# Connectors.net
KiCad netlist of a schematic drawn in Altium Designer
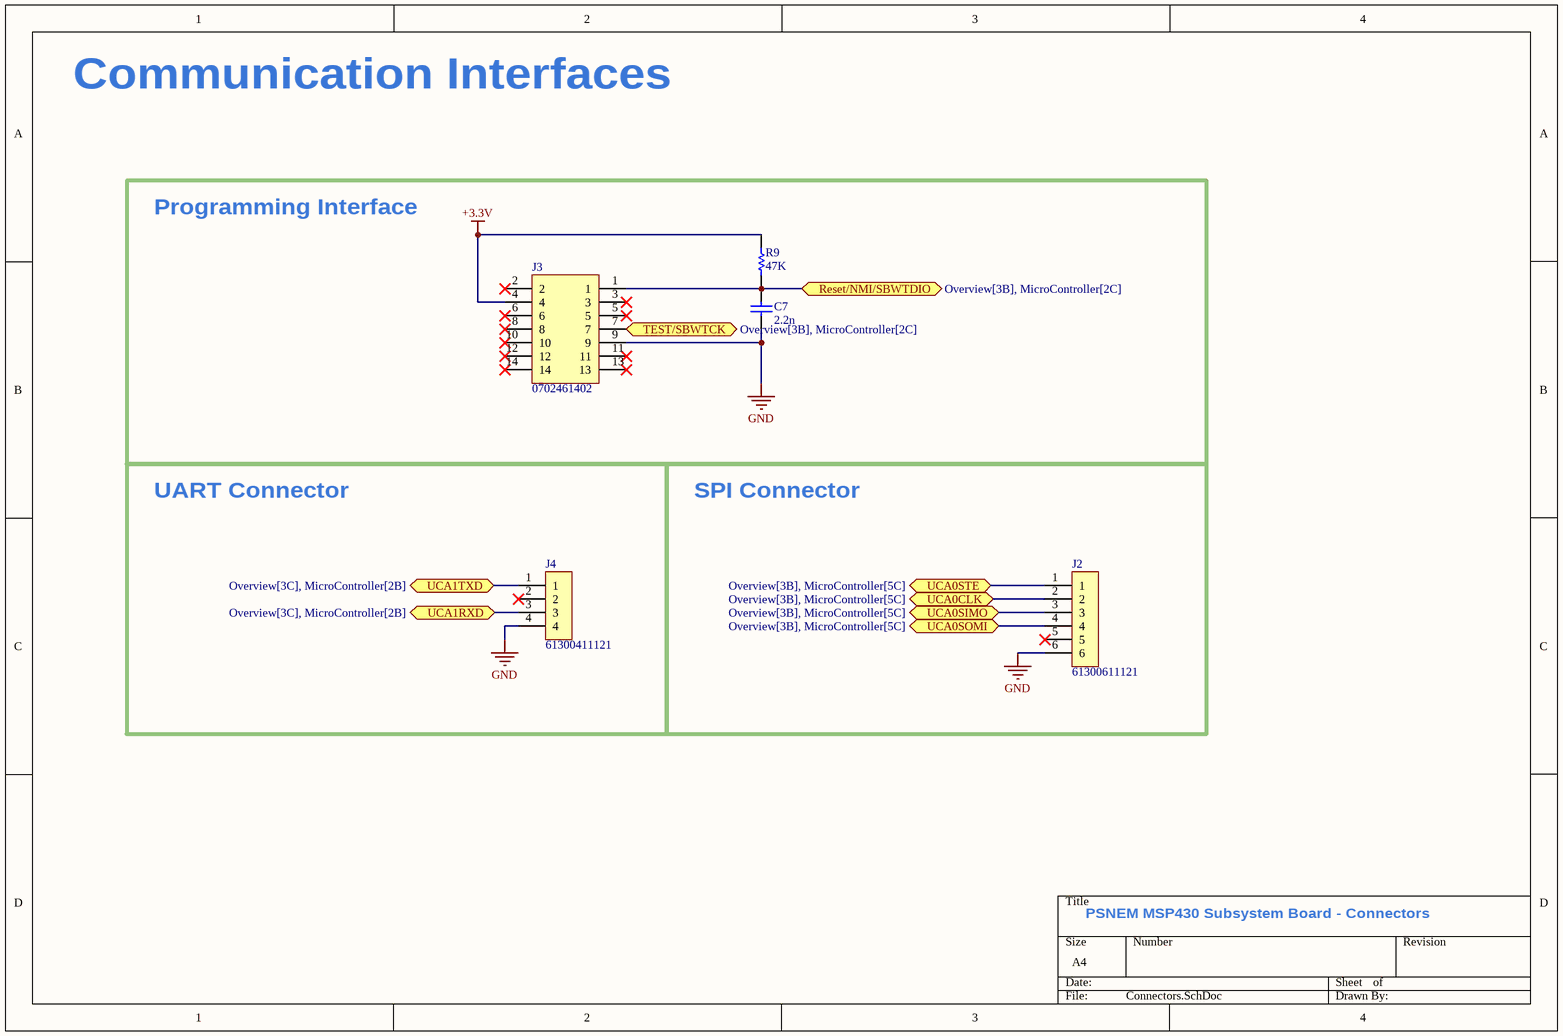
[diagram p0: Connectors.SchDoc]

(export (version "E")
  (design (tool "Eeschema 10.0.6"))
  (components
    (comp (ref "C7")
      (value "2.2n")
      (footprint "0805 Cap")
      (description "2200 pF ±10% 50V Ceramic Capacitor X7R 0805 (2012 Metric)")
      (libsource (lib "Schlib1") (part "CC0805KRX7R9BB222"))
    )
    (comp (ref "J2")
      (value "61300611121")
      (footprint "61300611121")
      (description "CONN HEADER VERT 6POS 2.54MM")
      (libsource (lib "Schlib1") (part "61300611121"))
    )
    (comp (ref "J3")
      (value "0702461402")
      (footprint "0702461402")
      (description "Connector Header Through Hole 14 position 0.100\" (2.54mm)")
      (libsource (lib "Schlib1") (part "0702461402"))
    )
    (comp (ref "J4")
      (value "61300411121")
      (footprint "61300411121")
      (description "Connector Header Through Hole 4 position 0.100\" (2.54mm)")
      (libsource (lib "Schlib1") (part "61300411121"))
    )
    (comp (ref "R9")
      (value "47K")
      (footprint "RESC1608X06N")
      (description "Thin Film Resistors - SMD 0603 0.1% 47Kohm 25ppm SMD")
      (libsource (lib "Schlib1") (part "ERA-3VEB4702V"))
    )
  )
  (nets
    (net (code "1") (name "+3.3V") (class "Default")
      (node (ref "J3") (pin "4") (pinfunction "4_4") (pintype "passive"))
      (node (ref "R9") (pin "2") (pinfunction "2_2") (pintype "passive"))
    )
    (net (code "2") (name "/Reset{slash}NMI{slash}SBWTDIO") (class "Default")
      (node (ref "C7") (pin "2") (pinfunction "2_2") (pintype "passive"))
      (node (ref "J3") (pin "1") (pinfunction "1_1") (pintype "passive"))
      (node (ref "R9") (pin "1") (pinfunction "1_1") (pintype "passive"))
    )
    (net (code "3") (name "/TEST{slash}SBWTCK") (class "Default")
      (node (ref "J3") (pin "7") (pinfunction "7_7") (pintype "passive"))
    )
    (net (code "4") (name "/UCA0CLK") (class "Default")
      (node (ref "J2") (pin "2") (pinfunction "2_2") (pintype "passive"))
    )
    (net (code "5") (name "/UCA0SIMO") (class "Default")
      (node (ref "J2") (pin "3") (pinfunction "3_3") (pintype "passive"))
    )
    (net (code "6") (name "/UCA0SOMI") (class "Default")
      (node (ref "J2") (pin "4") (pinfunction "4_4") (pintype "passive"))
    )
    (net (code "7") (name "/UCA0STE") (class "Default")
      (node (ref "J2") (pin "1") (pinfunction "1_1") (pintype "passive"))
    )
    (net (code "8") (name "/UCA1RXD") (class "Default")
      (node (ref "J4") (pin "3") (pinfunction "3_3") (pintype "passive"))
    )
    (net (code "9") (name "/UCA1TXD") (class "Default")
      (node (ref "J4") (pin "1") (pinfunction "1_1") (pintype "passive"))
    )
    (net (code "10") (name "GND") (class "Default")
      (node (ref "C7") (pin "1") (pinfunction "1_1") (pintype "passive"))
      (node (ref "J2") (pin "6") (pinfunction "6_6") (pintype "passive"))
      (node (ref "J3") (pin "9") (pinfunction "9_9") (pintype "passive"))
      (node (ref "J4") (pin "4") (pinfunction "4_4") (pintype "passive"))
    )
    (net (code "11") (name "unconnected-(J2-Pad5)") (class "Default")
      (node (ref "J2") (pin "5") (pinfunction "5_5") (pintype "passive+no_connect"))
    )
    (net (code "12") (name "unconnected-(J3-Pad2)") (class "Default")
      (node (ref "J3") (pin "2") (pinfunction "2_2") (pintype "passive+no_connect"))
    )
    (net (code "13") (name "unconnected-(J3-Pad3)") (class "Default")
      (node (ref "J3") (pin "3") (pinfunction "3_3") (pintype "passive+no_connect"))
    )
    (net (code "14") (name "unconnected-(J3-Pad5)") (class "Default")
      (node (ref "J3") (pin "5") (pinfunction "5_5") (pintype "passive+no_connect"))
    )
    (net (code "15") (name "unconnected-(J3-Pad6)") (class "Default")
      (node (ref "J3") (pin "6") (pinfunction "6_6") (pintype "passive+no_connect"))
    )
    (net (code "16") (name "unconnected-(J3-Pad8)") (class "Default")
      (node (ref "J3") (pin "8") (pinfunction "8_8") (pintype "passive+no_connect"))
    )
    (net (code "17") (name "unconnected-(J3-Pad10)") (class "Default")
      (node (ref "J3") (pin "10") (pinfunction "10_10") (pintype "passive+no_connect"))
    )
    (net (code "18") (name "unconnected-(J3-Pad11)") (class "Default")
      (node (ref "J3") (pin "11") (pinfunction "11_11") (pintype "passive+no_connect"))
    )
    (net (code "19") (name "unconnected-(J3-Pad12)") (class "Default")
      (node (ref "J3") (pin "12") (pinfunction "12_12") (pintype "passive+no_connect"))
    )
    (net (code "20") (name "unconnected-(J3-Pad13)") (class "Default")
      (node (ref "J3") (pin "13") (pinfunction "13_13") (pintype "passive+no_connect"))
    )
    (net (code "21") (name "unconnected-(J3-Pad14)") (class "Default")
      (node (ref "J3") (pin "14") (pinfunction "14_14") (pintype "passive+no_connect"))
    )
    (net (code "22") (name "unconnected-(J4-Pad2)") (class "Default")
      (node (ref "J4") (pin "2") (pinfunction "2_2") (pintype "passive+no_connect"))
    )
  )
)
